# ProProject_PetCareSTM32_MiniSTM32_2024-0.net
KiCad netlist of a schematic drawn in EasyEDA Pro
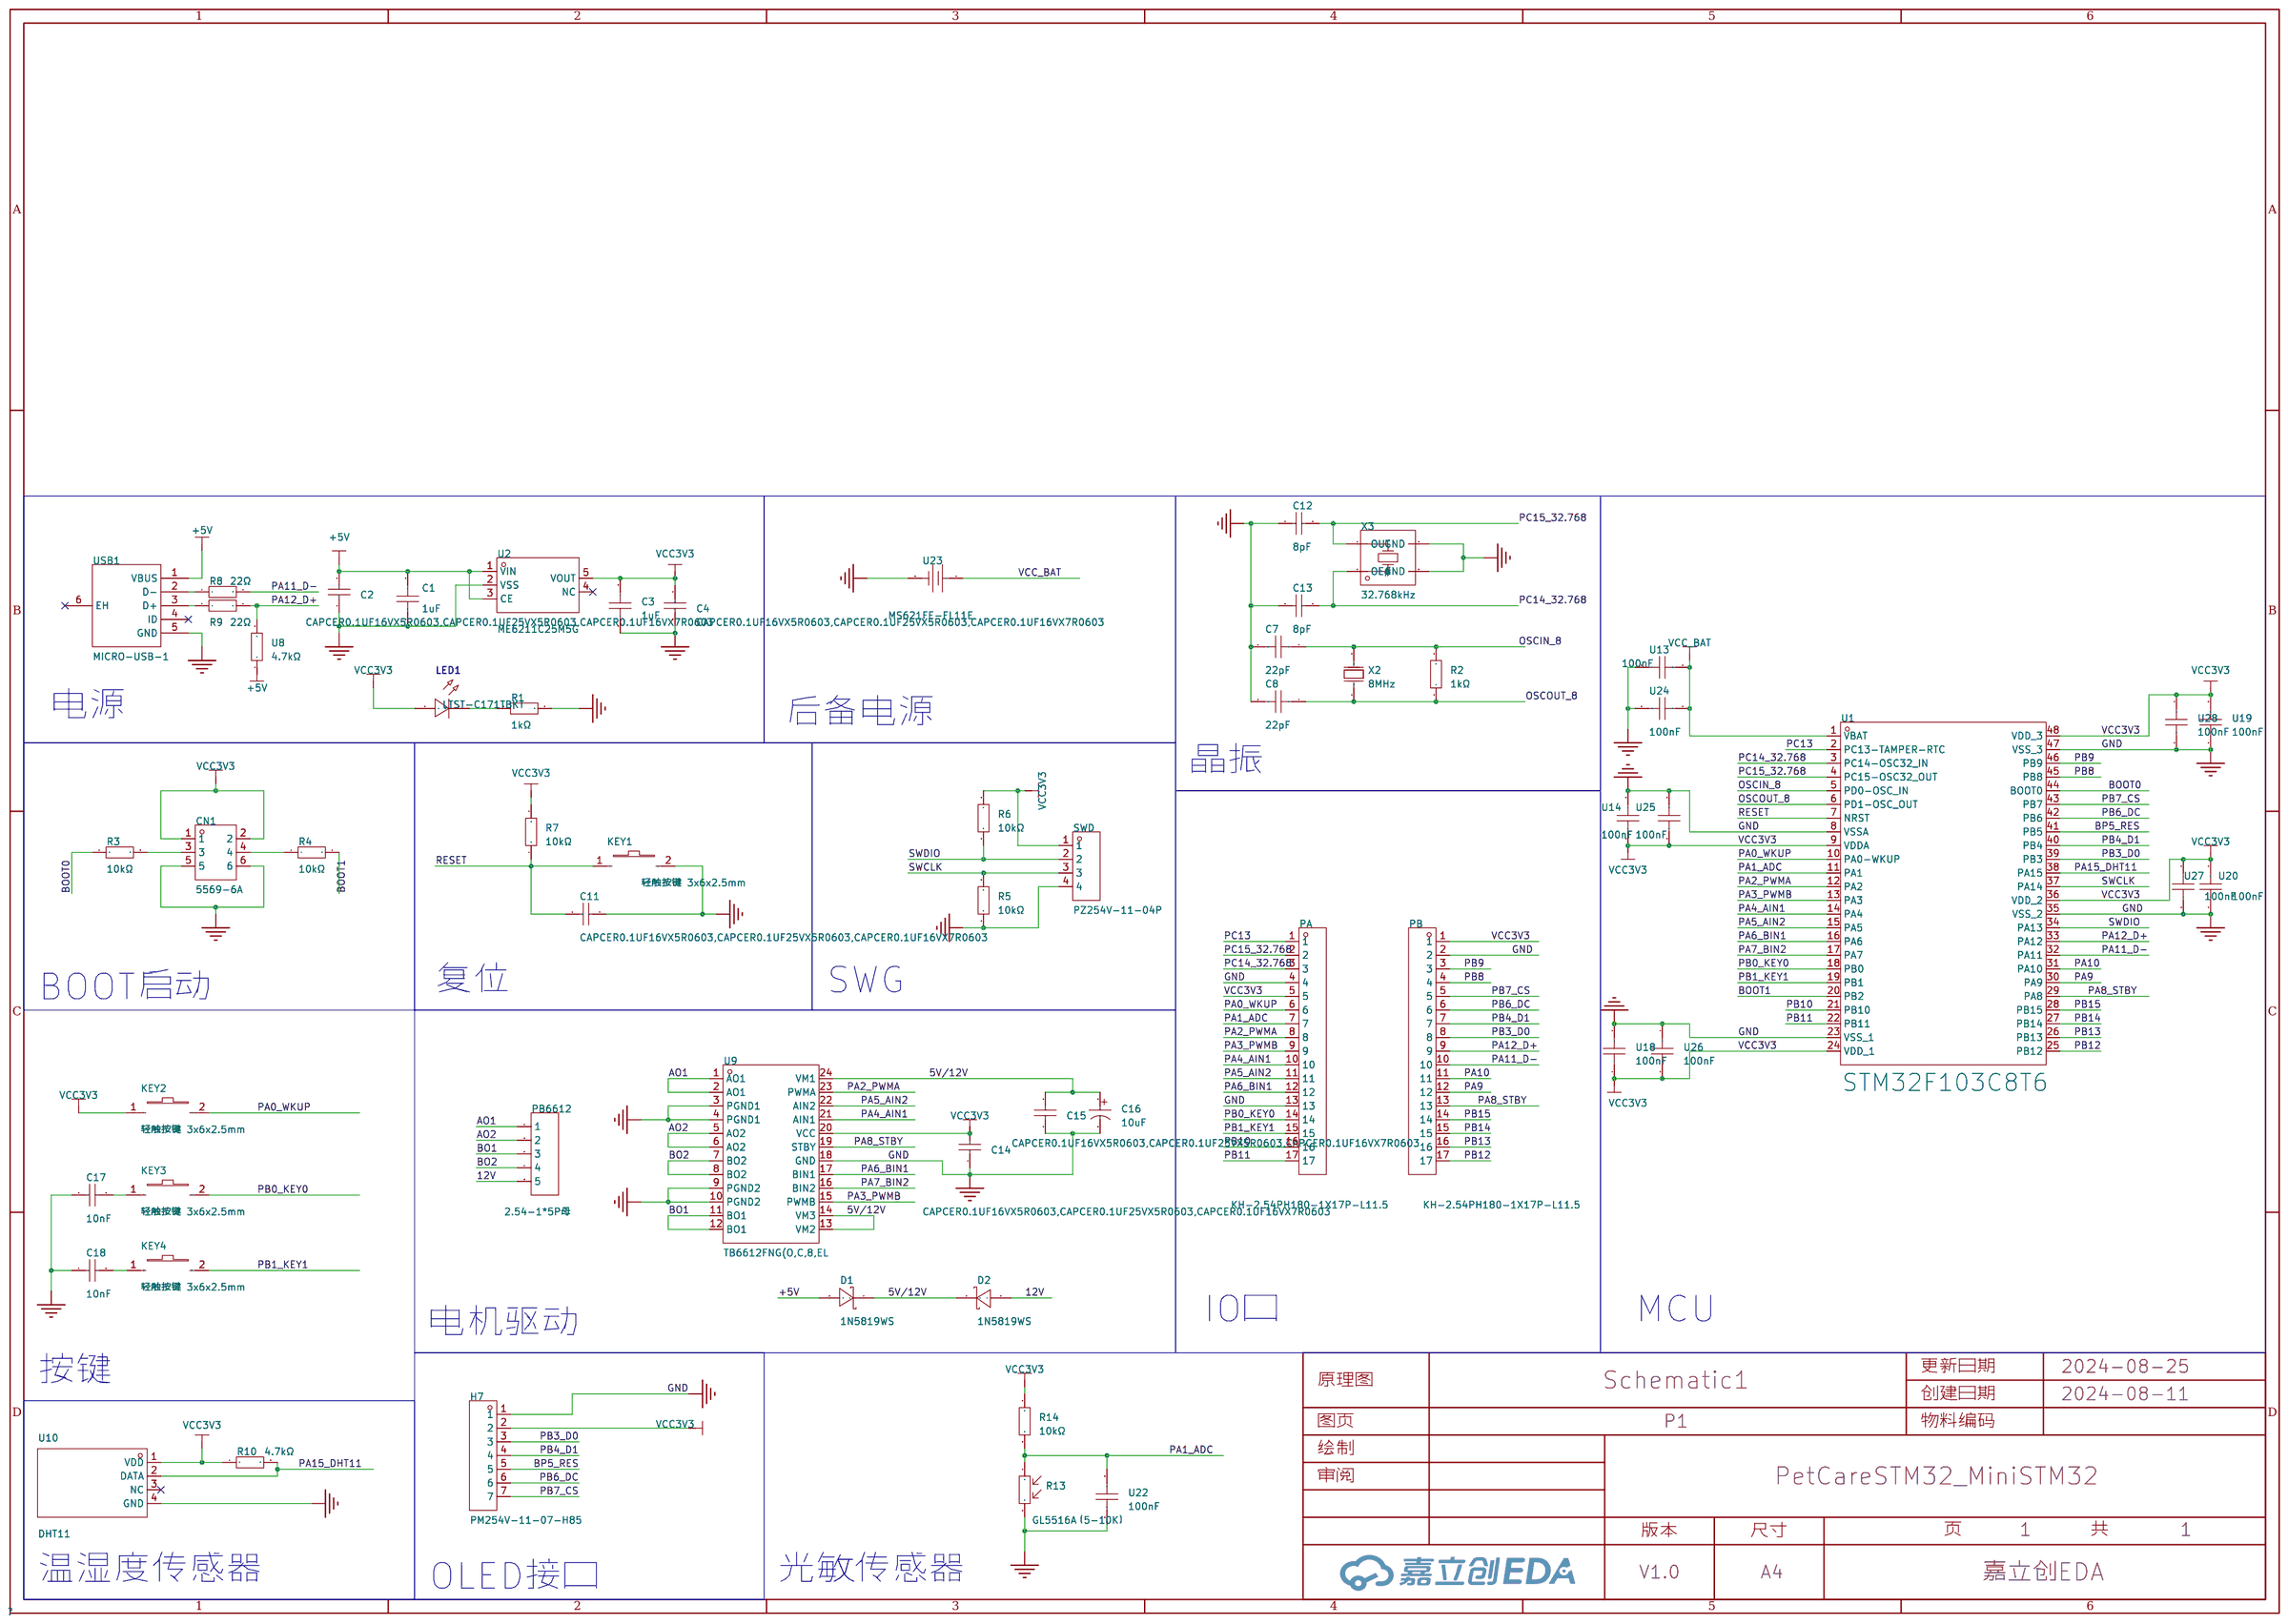
[diagram p0: schematic sheet]

(export (version "E")
  (design (tool "Eeschema 10.0.6"))
  (components
    (comp (ref "C1")
      (value "1uF")
      (footprint "easyedapro:C0603")
      (description "容值:1uF;精度:±10%;额定电压:50V;材质(温度系数):X5R;")
      (fields
        (field (name "Manufacturer Part") "CL10A105KB8NNNC")
        (field (name "Manufacturer") "SAMSUNG(三星)")
      )
      (libsource (lib "easyedapro") (part "CL10A105KB8NNNC"))
    )
    (comp (ref "C2")
      (value "CAPCER0.1UF16VX5R0603,CAPCER0.1UF25VX5R0603,CAPCER0.1UF16VX7R0603")
      (footprint "easyedapro:C0603")
      (libsource (lib "easyedapro") (part "CAPCER0.1UF16VX5R0603,CAPCER0.1UF25VX5R0603,CAPCER0.1UF16VX7R0603"))
    )
    (comp (ref "C3")
      (value "1uF")
      (footprint "easyedapro:C0603")
      (description "容值:1uF;精度:±10%;额定电压:50V;材质(温度系数):X5R;")
      (fields
        (field (name "Manufacturer Part") "CL10A105KB8NNNC")
        (field (name "Manufacturer") "SAMSUNG(三星)")
      )
      (libsource (lib "easyedapro") (part "CL10A105KB8NNNC"))
    )
    (comp (ref "C4")
      (value "CAPCER0.1UF16VX5R0603,CAPCER0.1UF25VX5R0603,CAPCER0.1UF16VX7R0603")
      (footprint "easyedapro:C0603")
      (libsource (lib "easyedapro") (part "CAPCER0.1UF16VX5R0603,CAPCER0.1UF25VX5R0603,CAPCER0.1UF16VX7R0603"))
    )
    (comp (ref "C7")
      (value "22pF")
      (footprint "easyedapro:C0603")
      (description "容值:22pF;精度:±5%;额定电压:50V;材质(温度系数):C0G;")
      (fields
        (field (name "Manufacturer Part") "CL10C220JB81PNC")
        (field (name "Manufacturer") "SAMSUNG(三星)")
      )
      (libsource (lib "easyedapro") (part "CL10C220JB81PNC"))
    )
    (comp (ref "C8")
      (value "22pF")
      (footprint "easyedapro:C0603")
      (description "容值:22pF;精度:±5%;额定电压:50V;材质(温度系数):C0G;")
      (fields
        (field (name "Manufacturer Part") "CL10C220JB81PNC")
        (field (name "Manufacturer") "SAMSUNG(三星)")
      )
      (libsource (lib "easyedapro") (part "CL10C220JB81PNC"))
    )
    (comp (ref "C11")
      (value "CAPCER0.1UF16VX5R0603,CAPCER0.1UF25VX5R0603,CAPCER0.1UF16VX7R0603")
      (footprint "easyedapro:C0603")
      (libsource (lib "easyedapro") (part "CAPCER0.1UF16VX5R0603,CAPCER0.1UF25VX5R0603,CAPCER0.1UF16VX7R0603"))
    )
    (comp (ref "C12")
      (value "8pF")
      (footprint "easyedapro:C0603")
      (description "容值:8pF;额定电压:50V;材质(温度系数):C0G;")
      (fields (field (name "Manufacturer Part") "0603CG8R0C500NT") (field (name "Manufacturer") "FH(风华)"))
      (libsource (lib "easyedapro") (part "0603CG8R0C500NT_C36508"))
    )
    (comp (ref "C13")
      (value "8pF")
      (footprint "easyedapro:C0603")
      (description "容值:8pF;额定电压:50V;材质(温度系数):C0G;")
      (fields (field (name "Manufacturer Part") "0603CG8R0C500NT") (field (name "Manufacturer") "FH(风华)"))
      (libsource (lib "easyedapro") (part "0603CG8R0C500NT_C36508"))
    )
    (comp (ref "C14")
      (value "CAPCER0.1UF16VX5R0603,CAPCER0.1UF25VX5R0603,CAPCER0.1UF16VX7R0603")
      (footprint "easyedapro:C0603")
      (libsource (lib "easyedapro") (part "CAPCER0.1UF16VX5R0603,CAPCER0.1UF25VX5R0603,CAPCER0.1UF16VX7R0603"))
    )
    (comp (ref "C15")
      (value "CAPCER0.1UF16VX5R0603,CAPCER0.1UF25VX5R0603,CAPCER0.1UF16VX7R0603")
      (footprint "easyedapro:C0603")
      (libsource (lib "easyedapro") (part "CAPCER0.1UF16VX5R0603,CAPCER0.1UF25VX5R0603,CAPCER0.1UF16VX7R0603"))
    )
    (comp (ref "C16")
      (value "10uF")
      (footprint "easyedapro:CAP-TH_BD5.0-P2.00-D0.8-FD")
      (description "容值:10uF;精度:±20%;额定电压:25V;")
      (fields (field (name "Manufacturer Part") "KF100M025C110A") (field (name "Manufacturer") "CapXon(丰宾)"))
      (libsource (lib "easyedapro") (part "KF100M025C110A"))
    )
    (comp (ref "C17")
      (value "10nF")
      (footprint "easyedapro:C0603")
      (description "容值:10nF;精度:±10%;额定电压:50V;材质(温度系数):X7R;")
      (fields
        (field (name "Manufacturer Part") "CC0603KRX7R9BB103")
        (field (name "Manufacturer") "YAGEO(国巨)")
      )
      (libsource (lib "easyedapro") (part "CC0603KRX7R9BB103"))
    )
    (comp (ref "C18")
      (value "10nF")
      (footprint "easyedapro:C0603")
      (description "容值:10nF;精度:±10%;额定电压:50V;材质(温度系数):X7R;")
      (fields
        (field (name "Manufacturer Part") "CC0603KRX7R9BB103")
        (field (name "Manufacturer") "YAGEO(国巨)")
      )
      (libsource (lib "easyedapro") (part "CC0603KRX7R9BB103"))
    )
    (comp (ref "CN1")
      (value "5569-6A")
      (footprint "easyedapro:CONN-TH_6P-P4.20_5569-6A-1")
      (libsource (lib "easyedapro") (part "5569-6A"))
    )
    (comp (ref "D1")
      (value "1N5819WS")
      (footprint "easyedapro:SOD-323_L1.8-W1.3-LS2.5-RD")
      (description "正向压降(Vf):600mV@1A;直流反向耐压(Vr):40V;平均整流电流(Io):1A;")
      (fields (field (name "Manufacturer") "Hottech(合科泰)"))
      (libsource (lib "easyedapro") (part "1N5819WS"))
    )
    (comp (ref "D2")
      (value "1N5819WS")
      (footprint "easyedapro:SOD-323_L1.8-W1.3-LS2.5-RD")
      (description "正向压降(Vf):600mV@1A;直流反向耐压(Vr):40V;平均整流电流(Io):1A;")
      (fields (field (name "Manufacturer") "Hottech(合科泰)"))
      (libsource (lib "easyedapro") (part "1N5819WS"))
    )
    (comp (ref "H7")
      (value "PM254V-11-07-H85")
      (footprint "easyedapro:HDR-TH_7P-P2.54-V-F")
      (fields (field (name "Manufacturer") "XFCN(兴飞)"))
      (libsource (lib "easyedapro") (part "PM254V-11-07-H85"))
    )
    (comp (ref "KEY1")
      (value "轻触按键 3x6x2.5mm")
      (footprint "easyedapro:SW-SMD_L6.0-W3.6-LS8.0")
      (libsource (lib "easyedapro") (part "3x6x2.5mm"))
    )
    (comp (ref "KEY2")
      (value "轻触按键 3x6x2.5mm")
      (footprint "easyedapro:SW-SMD_L6.0-W3.6-LS8.0")
      (libsource (lib "easyedapro") (part "3x6x2.5mm"))
    )
    (comp (ref "KEY3")
      (value "轻触按键 3x6x2.5mm")
      (footprint "easyedapro:SW-SMD_L6.0-W3.6-LS8.0")
      (libsource (lib "easyedapro") (part "3x6x2.5mm"))
    )
    (comp (ref "KEY4")
      (value "轻触按键 3x6x2.5mm")
      (footprint "easyedapro:SW-SMD_L6.0-W3.6-LS8.0")
      (libsource (lib "easyedapro") (part "3x6x2.5mm"))
    )
    (comp (ref "LED1")
      (value "LTST-C171TBKT")
      (footprint "easyedapro:LED_0805")
      (fields (field (name "Manufacturer") "LITEON(光宝)"))
      (libsource (lib "easyedapro") (part "LED_B"))
    )
    (comp (ref "PA")
      (value "KH-2.54PH180-1X17P-L11.5")
      (footprint "easyedapro:HDR-TH_17P-P2.54-V-M")
      (fields (field (name "Manufacturer") "kinghelm(金航标)"))
      (libsource (lib "easyedapro") (part "KH-2.54PH180-1X17P-L11.5"))
    )
    (comp (ref "PB")
      (value "KH-2.54PH180-1X17P-L11.5")
      (footprint "easyedapro:HDR-TH_17P-P2.54-V-M")
      (fields (field (name "Manufacturer") "kinghelm(金航标)"))
      (libsource (lib "easyedapro") (part "KH-2.54PH180-1X17P-L11.5"))
    )
    (comp (ref "PB6612")
      (value "2.54-1*5P母")
      (footprint "easyedapro:HDR-TH_5P-P2.54-V-F")
      (description "插孔结构:1x5P;间距:2.54mm;行距:-;安装类型:直插;排数:单排;总孔位数:5P;塑高:-;触头材质:-;触头镀层:-;")
      (fields (field (name "Manufacturer") "BOOMELE(博穆精密)"))
      (libsource (lib "easyedapro") (part "Header-Female-2.54_1x5"))
    )
    (comp (ref "R1")
      (value "1kΩ")
      (footprint "easyedapro:R0603")
      (description "电阻类型:厚膜电阻;阻值:1kΩ;精度:±1%;功率:100mW;最大工作电压:75V;温度系数:±100ppm/°C;")
      (fields (field (name "Manufacturer Part") "RC0603FR-071KL") (field (name "Manufacturer") "YAGEO(国巨)"))
      (libsource (lib "easyedapro") (part "RC0603FR-071KL"))
    )
    (comp (ref "R2")
      (value "1kΩ")
      (footprint "easyedapro:R0603")
      (description "电阻类型:厚膜电阻;阻值:1kΩ;精度:±0.5%;功率:100mW;最大工作电压:75V;温度系数:±100ppm/°C;")
      (fields
        (field (name "Manufacturer Part") "0603WAD1001T5E")
        (field (name "Manufacturer") "UNI-ROYAL(厚声)")
      )
      (libsource (lib "easyedapro") (part "0603WAD1001T5E"))
    )
    (comp (ref "R3")
      (value "10kΩ")
      (footprint "easyedapro:R0603")
      (description "电阻类型:厚膜电阻;阻值:10kΩ;精度:±1%;功率:100mW;最大工作电压:75V;温度系数:±100ppm/°C;")
      (fields
        (field (name "Manufacturer Part") "0603WAF1002T5E")
        (field (name "Manufacturer") "UNI-ROYAL(厚声)")
      )
      (libsource (lib "easyedapro") (part "0603WAF1002T5E"))
    )
    (comp (ref "R4")
      (value "10kΩ")
      (footprint "easyedapro:R0603")
      (description "电阻类型:厚膜电阻;阻值:10kΩ;精度:±1%;功率:100mW;最大工作电压:75V;温度系数:±100ppm/°C;")
      (fields
        (field (name "Manufacturer Part") "0603WAF1002T5E")
        (field (name "Manufacturer") "UNI-ROYAL(厚声)")
      )
      (libsource (lib "easyedapro") (part "0603WAF1002T5E"))
    )
    (comp (ref "R5")
      (value "10kΩ")
      (footprint "easyedapro:R0603")
      (description "电阻类型:厚膜电阻;阻值:10kΩ;精度:±1%;功率:100mW;最大工作电压:75V;温度系数:±100ppm/°C;")
      (fields
        (field (name "Manufacturer Part") "0603WAF1002T5E")
        (field (name "Manufacturer") "UNI-ROYAL(厚声)")
      )
      (libsource (lib "easyedapro") (part "0603WAF1002T5E"))
    )
    (comp (ref "R6")
      (value "10kΩ")
      (footprint "easyedapro:R0603")
      (description "电阻类型:厚膜电阻;阻值:10kΩ;精度:±1%;功率:100mW;最大工作电压:75V;温度系数:±100ppm/°C;")
      (fields
        (field (name "Manufacturer Part") "0603WAF1002T5E")
        (field (name "Manufacturer") "UNI-ROYAL(厚声)")
      )
      (libsource (lib "easyedapro") (part "0603WAF1002T5E"))
    )
    (comp (ref "R7")
      (value "10kΩ")
      (footprint "easyedapro:R0603")
      (description "电阻类型:厚膜电阻;阻值:10kΩ;精度:±1%;功率:100mW;最大工作电压:75V;温度系数:±100ppm/°C;")
      (fields
        (field (name "Manufacturer Part") "0603WAF1002T5E")
        (field (name "Manufacturer") "UNI-ROYAL(厚声)")
      )
      (libsource (lib "easyedapro") (part "0603WAF1002T5E"))
    )
    (comp (ref "R8")
      (value "22Ω")
      (footprint "easyedapro:R0805")
      (description "电阻类型:薄膜电阻;阻值:22Ω;精度:±1%;功率:250mW;最大工作电压:150V;温度系数:±25ppm/°C;")
      (fields
        (field (name "Manufacturer Part") "TC0525F220JT5E")
        (field (name "Manufacturer") "UNI-ROYAL(厚声)")
      )
      (libsource (lib "easyedapro") (part "TC0525F220JT5E"))
    )
    (comp (ref "R9")
      (value "22Ω")
      (footprint "easyedapro:R0805")
      (description "电阻类型:薄膜电阻;阻值:22Ω;精度:±1%;功率:250mW;最大工作电压:150V;温度系数:±25ppm/°C;")
      (fields
        (field (name "Manufacturer Part") "TC0525F220JT5E")
        (field (name "Manufacturer") "UNI-ROYAL(厚声)")
      )
      (libsource (lib "easyedapro") (part "TC0525F220JT5E"))
    )
    (comp (ref "R10")
      (value "4.7kΩ")
      (footprint "easyedapro:R1206")
      (description "电阻类型:厚膜电阻;阻值:4.7kΩ;精度:±1%;功率:250mW;最大工作电压:200V;温度系数:±100ppm/°C;")
      (fields
        (field (name "Manufacturer Part") "1206W4F4701T5E")
        (field (name "Manufacturer") "UNI-ROYAL(厚声)")
      )
      (libsource (lib "easyedapro") (part "1206W4F4701T5E"))
    )
    (comp (ref "R13")
      (value "GL5516A（5-10K）")
      (footprint "easyedapro:RES-TH_L5.1-W4.3-P3.40_GL55")
      (description "暗电阻:200kΩ;亮电阻 @ 10Lux:5kΩ~10kΩ;光谱峰值(波长):540nm;")
      (fields (field (name "Manufacturer") "JCHL(晶创和立)"))
      (libsource (lib "easyedapro") (part "GL5516A(5-10K)"))
    )
    (comp (ref "R14")
      (value "10kΩ")
      (footprint "easyedapro:R0603")
      (description "电阻类型:厚膜电阻;阻值:10kΩ;精度:±1%;功率:100mW;最大工作电压:75V;温度系数:±100ppm/°C;")
      (fields
        (field (name "Manufacturer Part") "0603WAF1002T5E")
        (field (name "Manufacturer") "UNI-ROYAL(厚声)")
      )
      (libsource (lib "easyedapro") (part "0603WAF1002T5E"))
    )
    (comp (ref "SWD")
      (value "PZ254V-11-04P")
      (footprint "easyedapro:HDR-TH_4P-P2.54-V-M")
      (fields (field (name "Manufacturer") "XFCN(兴飞)"))
      (libsource (lib "easyedapro") (part "PZ254V-11-04P_C2691448"))
    )
    (comp (ref "U1")
      (value "STM32F103C8T6")
      (footprint "easyedapro:LQFP-48_L7.0-W7.0-P0.50-LS9.0-BL")
      (description "CPU内核:ARM-M3;程序存储容量:64KB;RAM总容量:20KB;GPIO端口数量:37;工作电压范围:2V~3.6V;CPU最大主频:72MHz;程序存储器类型:FLASH;")
      (fields (field (name "Manufacturer") "ST(意法半导体)"))
      (libsource (lib "easyedapro") (part "STM32F103C8T6"))
    )
    (comp (ref "U2")
      (value "ME6211C25M5G")
      (footprint "easyedapro:SOT-23-5_L2.9-W1.7-P0.95-LS2.8-BL")
      (fields (field (name "Manufacturer") "MICRONE(南京微盟)"))
      (libsource (lib "easyedapro") (part "ME6211C25M5G"))
    )
    (comp (ref "U8")
      (value "4.7kΩ")
      (footprint "easyedapro:R0603")
      (description "电阻类型:薄膜电阻;阻值:4.7kΩ;精度:±1%;功率:100mW;最大工作电压:75V;温度系数:±50ppm/°C;")
      (fields (field (name "Manufacturer Part") "AR03FTDX4701A") (field (name "Manufacturer") "Viking(光颉)"))
      (libsource (lib "easyedapro") (part "AR03FTDX4701A"))
    )
    (comp (ref "U9")
      (value "TB6612FNG(O,C,8,EL")
      (footprint "easyedapro:SSOP-24_L8.4-W5.8-P0.65-LS7.8-BL")
      (description "双直流电机驱动器集成电路")
      (fields (field (name "Manufacturer") "TOSHIBA(东芝)"))
      (libsource (lib "easyedapro") (part "TB6612FNG(O,C,8,EL"))
    )
    (comp (ref "U10")
      (value "DHT11")
      (footprint "easyedapro:SENSOR-TH_DHT11")
      (description "新款电容式数字温湿度传感器,老款已停产16.1x12.6x5.8mm")
      (fields (field (name "Manufacturer") "广州奥松"))
      (libsource (lib "easyedapro") (part "DHT11"))
    )
    (comp (ref "U13")
      (value "100nF")
      (footprint "easyedapro:C0603")
      (description "容值:100nF;精度:±10%;额定电压:50V;材质(温度系数):X7R;")
      (fields
        (field (name "Manufacturer Part") "CGA0603X7R104K500JT")
        (field (name "Manufacturer") "HRE(芯声)")
      )
      (libsource (lib "easyedapro") (part "CGA0603X7R104K500JT"))
    )
    (comp (ref "U14")
      (value "100nF")
      (footprint "easyedapro:C0603")
      (description "容值:100nF;精度:±10%;额定电压:50V;材质(温度系数):X7R;")
      (fields
        (field (name "Manufacturer Part") "CGA0603X7R104K500JT")
        (field (name "Manufacturer") "HRE(芯声)")
      )
      (libsource (lib "easyedapro") (part "CGA0603X7R104K500JT"))
    )
    (comp (ref "U18")
      (value "100nF")
      (footprint "easyedapro:C0603")
      (description "容值:100nF;精度:±10%;额定电压:50V;材质(温度系数):X7R;")
      (fields
        (field (name "Manufacturer Part") "CGA0603X7R104K500JT")
        (field (name "Manufacturer") "HRE(芯声)")
      )
      (libsource (lib "easyedapro") (part "CGA0603X7R104K500JT"))
    )
    (comp (ref "U19")
      (value "100nF")
      (footprint "easyedapro:C0603")
      (description "容值:100nF;精度:±10%;额定电压:50V;材质(温度系数):X7R;")
      (fields
        (field (name "Manufacturer Part") "CGA0603X7R104K500JT")
        (field (name "Manufacturer") "HRE(芯声)")
      )
      (libsource (lib "easyedapro") (part "CGA0603X7R104K500JT"))
    )
    (comp (ref "U20")
      (value "100nF")
      (footprint "easyedapro:C0603")
      (description "容值:100nF;精度:±10%;额定电压:50V;材质(温度系数):X7R;")
      (fields
        (field (name "Manufacturer Part") "CGA0603X7R104K500JT")
        (field (name "Manufacturer") "HRE(芯声)")
      )
      (libsource (lib "easyedapro") (part "CGA0603X7R104K500JT"))
    )
    (comp (ref "U22")
      (value "100nF")
      (footprint "easyedapro:C0603")
      (description "容值:100nF;精度:±10%;额定电压:50V;材质(温度系数):X7R;")
      (fields
        (field (name "Manufacturer Part") "CGA0603X7R104K500JT")
        (field (name "Manufacturer") "HRE(芯声)")
      )
      (libsource (lib "easyedapro") (part "CGA0603X7R104K500JT"))
    )
    (comp (ref "U23")
      (value "MS621FE-FL11E")
      (footprint "easyedapro:BAT-SMD_FL11E")
      (description "FL11E 3.3V可充电纽扣电池 5.5mAH")
      (fields (field (name "Manufacturer") "Seiko(精工)"))
      (libsource (lib "easyedapro") (part "MS621FE-FL11E"))
    )
    (comp (ref "U24")
      (value "100nF")
      (footprint "easyedapro:C0603")
      (description "容值:100nF;精度:±10%;额定电压:50V;材质(温度系数):X7R;")
      (fields
        (field (name "Manufacturer Part") "CGA0603X7R104K500JT")
        (field (name "Manufacturer") "HRE(芯声)")
      )
      (libsource (lib "easyedapro") (part "CGA0603X7R104K500JT"))
    )
    (comp (ref "U25")
      (value "100nF")
      (footprint "easyedapro:C0603")
      (description "容值:100nF;精度:±10%;额定电压:50V;材质(温度系数):X7R;")
      (fields
        (field (name "Manufacturer Part") "CGA0603X7R104K500JT")
        (field (name "Manufacturer") "HRE(芯声)")
      )
      (libsource (lib "easyedapro") (part "CGA0603X7R104K500JT"))
    )
    (comp (ref "U26")
      (value "100nF")
      (footprint "easyedapro:C0603")
      (description "容值:100nF;精度:±10%;额定电压:50V;材质(温度系数):X7R;")
      (fields
        (field (name "Manufacturer Part") "CGA0603X7R104K500JT")
        (field (name "Manufacturer") "HRE(芯声)")
      )
      (libsource (lib "easyedapro") (part "CGA0603X7R104K500JT"))
    )
    (comp (ref "U27")
      (value "100nF")
      (footprint "easyedapro:C0603")
      (description "容值:100nF;精度:±10%;额定电压:50V;材质(温度系数):X7R;")
      (fields
        (field (name "Manufacturer Part") "CGA0603X7R104K500JT")
        (field (name "Manufacturer") "HRE(芯声)")
      )
      (libsource (lib "easyedapro") (part "CGA0603X7R104K500JT"))
    )
    (comp (ref "U28")
      (value "100nF")
      (footprint "easyedapro:C0603")
      (description "容值:100nF;精度:±10%;额定电压:50V;材质(温度系数):X7R;")
      (fields
        (field (name "Manufacturer Part") "CGA0603X7R104K500JT")
        (field (name "Manufacturer") "HRE(芯声)")
      )
      (libsource (lib "easyedapro") (part "CGA0603X7R104K500JT"))
    )
    (comp (ref "USB1")
      (value "MICRO-USB-1")
      (footprint "easyedapro:MICRO-USB-SMD_C9900008946")
      (libsource (lib "easyedapro") (part "MICRO-USB-1"))
    )
    (comp (ref "X2")
      (value "8MHz")
      (footprint "easyedapro:OSC-SMD_L5.0-W3.2")
      (description "晶振类型:贴片晶振;频率:8MHz;常温频差:±20ppm;外接负载电容:18pF;频率稳定度(全温):±30ppm;")
      (fields
        (field (name "Manufacturer Part") "ABM3-8.000MHZ-D2Y-T")
        (field (name "Manufacturer") "ABRACON")
      )
      (libsource (lib "easyedapro") (part "ABM3-8.000MHZ-D2Y-T"))
    )
    (comp (ref "X3")
      (value "32.768kHz")
      (footprint "easyedapro:CRYSTAL-SMD_4P-L8.0-W3.8-BL")
      (description "晶振类型:-;频率:32.768kHz;常温频差:±20ppm;外接负载电容:12.5pF;频率稳定度(全温):-;")
      (fields (field (name "Manufacturer Part") "ABS25-32.768KHZ-T") (field (name "Manufacturer") "ABRACON"))
      (libsource (lib "easyedapro") (part "ABS25-32.768KHZ-T"))
    )
  )
  (nets
    (net (code "1") (name "+5V") (class "Default")
      (node (ref "C1") (pin "2") (pinfunction "2_2") (pintype "unspecified"))
      (node (ref "C2") (pin "2") (pinfunction "2_2") (pintype "input"))
      (node (ref "D1") (pin "2") (pinfunction "A_2") (pintype "unspecified"))
      (node (ref "U2") (pin "1") (pinfunction "VIN_1") (pintype "unspecified"))
      (node (ref "U2") (pin "3") (pinfunction "CE_3") (pintype "unspecified"))
      (node (ref "U8") (pin "1") (pinfunction "1_1") (pintype "unspecified"))
      (node (ref "USB1") (pin "1") (pinfunction "VBUS_1") (pintype "input"))
    )
    (net (code "2") (name "/5V{slash}12V") (class "Default")
      (node (ref "C15") (pin "2") (pinfunction "2_2") (pintype "input"))
      (node (ref "C16") (pin "1") (pinfunction "1_1") (pintype "input"))
      (node (ref "D1") (pin "1") (pinfunction "K_1") (pintype "unspecified"))
      (node (ref "D2") (pin "1") (pinfunction "K_1") (pintype "unspecified"))
      (node (ref "U9") (pin "13") (pinfunction "VM2_13") (pintype "unspecified"))
      (node (ref "U9") (pin "14") (pinfunction "VM3_14") (pintype "unspecified"))
      (node (ref "U9") (pin "24") (pinfunction "VM1_24") (pintype "unspecified"))
    )
    (net (code "3") (name "/12V") (class "Default")
      (node (ref "D2") (pin "2") (pinfunction "A_2") (pintype "unspecified"))
      (node (ref "PB6612") (pin "5") (pinfunction "5_5") (pintype "input"))
    )
    (net (code "4") (name "/AO1") (class "Default")
      (node (ref "PB6612") (pin "1") (pinfunction "1_1") (pintype "input"))
      (node (ref "U9") (pin "1") (pinfunction "AO1_1") (pintype "unspecified"))
      (node (ref "U9") (pin "2") (pinfunction "AO1_2") (pintype "unspecified"))
    )
    (net (code "5") (name "/AO2") (class "Default")
      (node (ref "PB6612") (pin "2") (pinfunction "2_2") (pintype "input"))
      (node (ref "U9") (pin "5") (pinfunction "AO2_5") (pintype "unspecified"))
      (node (ref "U9") (pin "6") (pinfunction "AO2_6") (pintype "unspecified"))
    )
    (net (code "6") (name "/BO1") (class "Default")
      (node (ref "PB6612") (pin "3") (pinfunction "3_3") (pintype "input"))
      (node (ref "U9") (pin "11") (pinfunction "BO1_11") (pintype "unspecified"))
      (node (ref "U9") (pin "12") (pinfunction "BO1_12") (pintype "unspecified"))
    )
    (net (code "7") (name "/BO2") (class "Default")
      (node (ref "PB6612") (pin "4") (pinfunction "4_4") (pintype "input"))
      (node (ref "U9") (pin "7") (pinfunction "BO2_7") (pintype "unspecified"))
      (node (ref "U9") (pin "8") (pinfunction "BO2_8") (pintype "unspecified"))
    )
    (net (code "8") (name "/BOOT0") (class "Default")
      (node (ref "R3") (pin "1") (pinfunction "1_1") (pintype "input"))
      (node (ref "U1") (pin "44") (pinfunction "BOOT0_44") (pintype "unspecified"))
    )
    (net (code "9") (name "/BOOT1") (class "Default")
      (node (ref "R4") (pin "2") (pinfunction "2_2") (pintype "input"))
      (node (ref "U1") (pin "20") (pinfunction "PB2_20") (pintype "unspecified"))
    )
    (net (code "10") (name "/BP5_RES") (class "Default")
      (node (ref "H7") (pin "5") (pinfunction "5_5") (pintype "unspecified"))
      (node (ref "U1") (pin "41") (pinfunction "PB5_41") (pintype "unspecified"))
    )
    (net (code "11") (name "/OSCIN_8") (class "Default")
      (node (ref "C7") (pin "1") (pinfunction "1_1") (pintype "unspecified"))
      (node (ref "R2") (pin "2") (pinfunction "2_2") (pintype "input"))
      (node (ref "U1") (pin "5") (pinfunction "PD0-OSC_IN_5") (pintype "unspecified"))
      (node (ref "X2") (pin "2") (pinfunction "OSC2_2") (pintype "input"))
    )
    (net (code "12") (name "/OSCOUT_8") (class "Default")
      (node (ref "C8") (pin "1") (pinfunction "1_1") (pintype "unspecified"))
      (node (ref "R2") (pin "1") (pinfunction "1_1") (pintype "input"))
      (node (ref "U1") (pin "6") (pinfunction "PD1-OSC_OUT_6") (pintype "unspecified"))
      (node (ref "X2") (pin "1") (pinfunction "OSC1_1") (pintype "input"))
    )
    (net (code "13") (name "/PA0_WKUP") (class "Default")
      (node (ref "KEY2") (pin "2") (pinfunction "2_2") (pintype "input"))
      (node (ref "PA") (pin "6") (pinfunction "6_6") (pintype "unspecified"))
      (node (ref "U1") (pin "10") (pinfunction "PA0-WKUP_10") (pintype "unspecified"))
    )
    (net (code "14") (name "/PA1_ADC") (class "Default")
      (node (ref "PA") (pin "7") (pinfunction "7_7") (pintype "unspecified"))
      (node (ref "R13") (pin "1") (pinfunction "1_1") (pintype "input"))
      (node (ref "R14") (pin "1") (pinfunction "1_1") (pintype "input"))
      (node (ref "U1") (pin "11") (pinfunction "PA1_11") (pintype "unspecified"))
      (node (ref "U22") (pin "2") (pinfunction "2_2") (pintype "unspecified"))
    )
    (net (code "15") (name "/PA2_PWMA") (class "Default")
      (node (ref "PA") (pin "8") (pinfunction "8_8") (pintype "unspecified"))
      (node (ref "U1") (pin "12") (pinfunction "PA2_12") (pintype "unspecified"))
      (node (ref "U9") (pin "23") (pinfunction "PWMA_23") (pintype "unspecified"))
    )
    (net (code "16") (name "/PA3_PWMB") (class "Default")
      (node (ref "PA") (pin "9") (pinfunction "9_9") (pintype "unspecified"))
      (node (ref "U1") (pin "13") (pinfunction "PA3_13") (pintype "unspecified"))
      (node (ref "U9") (pin "15") (pinfunction "PWMB_15") (pintype "unspecified"))
    )
    (net (code "17") (name "/PA4_AIN1") (class "Default")
      (node (ref "PA") (pin "10") (pinfunction "10_10") (pintype "unspecified"))
      (node (ref "U1") (pin "14") (pinfunction "PA4_14") (pintype "unspecified"))
      (node (ref "U9") (pin "21") (pinfunction "AIN1_21") (pintype "unspecified"))
    )
    (net (code "18") (name "/PA5_AIN2") (class "Default")
      (node (ref "PA") (pin "11") (pinfunction "11_11") (pintype "unspecified"))
      (node (ref "U1") (pin "15") (pinfunction "PA5_15") (pintype "unspecified"))
      (node (ref "U9") (pin "22") (pinfunction "AIN2_22") (pintype "unspecified"))
    )
    (net (code "19") (name "/PA6_BIN1") (class "Default")
      (node (ref "PA") (pin "12") (pinfunction "12_12") (pintype "unspecified"))
      (node (ref "U1") (pin "16") (pinfunction "PA6_16") (pintype "unspecified"))
      (node (ref "U9") (pin "17") (pinfunction "BIN1_17") (pintype "unspecified"))
    )
    (net (code "20") (name "/PA7_BIN2") (class "Default")
      (node (ref "U1") (pin "17") (pinfunction "PA7_17") (pintype "unspecified"))
      (node (ref "U9") (pin "16") (pinfunction "BIN2_16") (pintype "unspecified"))
    )
    (net (code "21") (name "/PA8_STBY") (class "Default")
      (node (ref "PB") (pin "13") (pinfunction "13_13") (pintype "unspecified"))
      (node (ref "U1") (pin "29") (pinfunction "PA8_29") (pintype "unspecified"))
      (node (ref "U9") (pin "19") (pinfunction "STBY_19") (pintype "unspecified"))
    )
    (net (code "22") (name "/PA9") (class "Default")
      (node (ref "PB") (pin "12") (pinfunction "12_12") (pintype "unspecified"))
      (node (ref "U1") (pin "30") (pinfunction "PA9_30") (pintype "unspecified"))
    )
    (net (code "23") (name "/PA10") (class "Default")
      (node (ref "PB") (pin "11") (pinfunction "11_11") (pintype "unspecified"))
      (node (ref "U1") (pin "31") (pinfunction "PA10_31") (pintype "unspecified"))
    )
    (net (code "24") (name "/PA11_D-") (class "Default")
      (node (ref "PB") (pin "10") (pinfunction "10_10") (pintype "unspecified"))
      (node (ref "R8") (pin "2") (pinfunction "2_2") (pintype "input"))
      (node (ref "U1") (pin "32") (pinfunction "PA11_32") (pintype "unspecified"))
    )
    (net (code "25") (name "/PA12_D+") (class "Default")
      (node (ref "PB") (pin "9") (pinfunction "9_9") (pintype "unspecified"))
      (node (ref "R9") (pin "2") (pinfunction "2_2") (pintype "input"))
      (node (ref "U1") (pin "33") (pinfunction "PA12_33") (pintype "unspecified"))
      (node (ref "U8") (pin "2") (pinfunction "2_2") (pintype "unspecified"))
    )
    (net (code "26") (name "/PA15_DHT11") (class "Default")
      (node (ref "R10") (pin "2") (pinfunction "2_2") (pintype "input"))
      (node (ref "U1") (pin "38") (pinfunction "PA15_38") (pintype "unspecified"))
      (node (ref "U10") (pin "2") (pinfunction "DATA_2") (pintype "unspecified"))
    )
    (net (code "27") (name "/PB0_KEY0") (class "Default")
      (node (ref "KEY3") (pin "2") (pinfunction "2_2") (pintype "input"))
      (node (ref "PA") (pin "14") (pinfunction "14_14") (pintype "unspecified"))
      (node (ref "U1") (pin "18") (pinfunction "PB0_18") (pintype "unspecified"))
    )
    (net (code "28") (name "/PB1_KEY1") (class "Default")
      (node (ref "KEY4") (pin "2") (pinfunction "2_2") (pintype "input"))
      (node (ref "PA") (pin "15") (pinfunction "15_15") (pintype "unspecified"))
      (node (ref "U1") (pin "19") (pinfunction "PB1_19") (pintype "unspecified"))
    )
    (net (code "29") (name "/PB3_D0") (class "Default")
      (node (ref "H7") (pin "3") (pinfunction "3_3") (pintype "unspecified"))
      (node (ref "PB") (pin "8") (pinfunction "8_8") (pintype "unspecified"))
      (node (ref "U1") (pin "39") (pinfunction "PB3_39") (pintype "unspecified"))
    )
    (net (code "30") (name "/PB4_D1") (class "Default")
      (node (ref "H7") (pin "4") (pinfunction "4_4") (pintype "unspecified"))
      (node (ref "PB") (pin "7") (pinfunction "7_7") (pintype "unspecified"))
      (node (ref "U1") (pin "40") (pinfunction "PB4_40") (pintype "unspecified"))
    )
    (net (code "31") (name "/PB6_DC") (class "Default")
      (node (ref "H7") (pin "6") (pinfunction "6_6") (pintype "unspecified"))
      (node (ref "PB") (pin "6") (pinfunction "6_6") (pintype "unspecified"))
      (node (ref "U1") (pin "42") (pinfunction "PB6_42") (pintype "unspecified"))
    )
    (net (code "32") (name "/PB7_CS") (class "Default")
      (node (ref "H7") (pin "7") (pinfunction "7_7") (pintype "unspecified"))
      (node (ref "PB") (pin "5") (pinfunction "5_5") (pintype "unspecified"))
      (node (ref "U1") (pin "43") (pinfunction "PB7_43") (pintype "unspecified"))
    )
    (net (code "33") (name "/PB8") (class "Default")
      (node (ref "PB") (pin "4") (pinfunction "4_4") (pintype "unspecified"))
      (node (ref "U1") (pin "45") (pinfunction "PB8_45") (pintype "unspecified"))
    )
    (net (code "34") (name "/PB9") (class "Default")
      (node (ref "PB") (pin "3") (pinfunction "3_3") (pintype "unspecified"))
      (node (ref "U1") (pin "46") (pinfunction "PB9_46") (pintype "unspecified"))
    )
    (net (code "35") (name "/PB10") (class "Default")
      (node (ref "PA") (pin "16") (pinfunction "16_16") (pintype "unspecified"))
      (node (ref "U1") (pin "21") (pinfunction "PB10_21") (pintype "unspecified"))
    )
    (net (code "36") (name "/PB11") (class "Default")
      (node (ref "PA") (pin "17") (pinfunction "17_17") (pintype "unspecified"))
      (node (ref "U1") (pin "22") (pinfunction "PB11_22") (pintype "unspecified"))
    )
    (net (code "37") (name "/PB12") (class "Default")
      (node (ref "PB") (pin "17") (pinfunction "17_17") (pintype "unspecified"))
      (node (ref "U1") (pin "25") (pinfunction "PB12_25") (pintype "unspecified"))
    )
    (net (code "38") (name "/PB13") (class "Default")
      (node (ref "PB") (pin "16") (pinfunction "16_16") (pintype "unspecified"))
      (node (ref "U1") (pin "26") (pinfunction "PB13_26") (pintype "unspecified"))
    )
    (net (code "39") (name "/PB14") (class "Default")
      (node (ref "PB") (pin "15") (pinfunction "15_15") (pintype "unspecified"))
      (node (ref "U1") (pin "27") (pinfunction "PB14_27") (pintype "unspecified"))
    )
    (net (code "40") (name "/PB15") (class "Default")
      (node (ref "PB") (pin "14") (pinfunction "14_14") (pintype "unspecified"))
      (node (ref "U1") (pin "28") (pinfunction "PB15_28") (pintype "unspecified"))
    )
    (net (code "41") (name "/PC13") (class "Default")
      (node (ref "PA") (pin "1") (pinfunction "1_1") (pintype "unspecified"))
      (node (ref "U1") (pin "2") (pinfunction "PC13-TAMPER-RTC_2") (pintype "unspecified"))
    )
    (net (code "42") (name "/PC14_32.768") (class "Default")
      (node (ref "C13") (pin "2") (pinfunction "2_2") (pintype "input"))
      (node (ref "PA") (pin "3") (pinfunction "3_3") (pintype "unspecified"))
      (node (ref "U1") (pin "3") (pinfunction "PC14-OSC32_IN_3") (pintype "unspecified"))
      (node (ref "X3") (pin "1") (pinfunction "OE#_1") (pintype "input"))
    )
    (net (code "43") (name "/PC15_32.768") (class "Default")
      (node (ref "C12") (pin "2") (pinfunction "2_2") (pintype "input"))
      (node (ref "PA") (pin "2") (pinfunction "2_2") (pintype "unspecified"))
      (node (ref "U1") (pin "4") (pinfunction "PC15-OSC32_OUT_4") (pintype "unspecified"))
      (node (ref "X3") (pin "4") (pinfunction "OUT_4") (pintype "input"))
    )
    (net (code "44") (name "/RESET") (class "Default")
      (node (ref "C11") (pin "1") (pinfunction "1_1") (pintype "input"))
      (node (ref "KEY1") (pin "1") (pinfunction "1_1") (pintype "input"))
      (node (ref "R7") (pin "1") (pinfunction "1_1") (pintype "input"))
      (node (ref "U1") (pin "7") (pinfunction "NRST_7") (pintype "unspecified"))
    )
    (net (code "45") (name "/SWCLK") (class "Default")
      (node (ref "R5") (pin "2") (pinfunction "2_2") (pintype "input"))
      (node (ref "SWD") (pin "3") (pinfunction "3_3") (pintype "unspecified"))
      (node (ref "U1") (pin "37") (pinfunction "PA14_37") (pintype "unspecified"))
    )
    (net (code "46") (name "/SWDIO") (class "Default")
      (node (ref "R6") (pin "1") (pinfunction "1_1") (pintype "input"))
      (node (ref "SWD") (pin "2") (pinfunction "2_2") (pintype "unspecified"))
      (node (ref "U1") (pin "34") (pinfunction "PA13_34") (pintype "unspecified"))
    )
    (net (code "47") (name "GND") (class "Default")
      (node (ref "C1") (pin "1") (pinfunction "1_1") (pintype "unspecified"))
      (node (ref "C11") (pin "2") (pinfunction "2_2") (pintype "input"))
      (node (ref "C12") (pin "1") (pinfunction "1_1") (pintype "input"))
      (node (ref "C13") (pin "1") (pinfunction "1_1") (pintype "input"))
      (node (ref "C14") (pin "1") (pinfunction "1_1") (pintype "input"))
      (node (ref "C15") (pin "1") (pinfunction "1_1") (pintype "input"))
      (node (ref "C16") (pin "2") (pinfunction "2_2") (pintype "input"))
      (node (ref "C17") (pin "2") (pinfunction "2_2") (pintype "input"))
      (node (ref "C18") (pin "1") (pinfunction "1_1") (pintype "input"))
      (node (ref "C2") (pin "1") (pinfunction "1_1") (pintype "input"))
      (node (ref "C3") (pin "1") (pinfunction "1_1") (pintype "unspecified"))
      (node (ref "C4") (pin "1") (pinfunction "1_1") (pintype "input"))
      (node (ref "C7") (pin "2") (pinfunction "2_2") (pintype "unspecified"))
      (node (ref "C8") (pin "2") (pinfunction "2_2") (pintype "unspecified"))
      (node (ref "CN1") (pin "5") (pinfunction "5_5") (pintype "unspecified"))
      (node (ref "CN1") (pin "6") (pinfunction "6_6") (pintype "unspecified"))
      (node (ref "H7") (pin "1") (pinfunction "1_1") (pintype "unspecified"))
      (node (ref "KEY1") (pin "2") (pinfunction "2_2") (pintype "input"))
      (node (ref "PA") (pin "13") (pinfunction "13_13") (pintype "unspecified"))
      (node (ref "PA") (pin "4") (pinfunction "4_4") (pintype "unspecified"))
      (node (ref "PB") (pin "2") (pinfunction "2_2") (pintype "unspecified"))
      (node (ref "R1") (pin "2") (pinfunction "2_2") (pintype "input"))
      (node (ref "R13") (pin "2") (pinfunction "2_2") (pintype "input"))
      (node (ref "R5") (pin "1") (pinfunction "1_1") (pintype "input"))
      (node (ref "SWD") (pin "4") (pinfunction "4_4") (pintype "unspecified"))
      (node (ref "U1") (pin "23") (pinfunction "VSS_1_23") (pintype "unspecified"))
      (node (ref "U1") (pin "35") (pinfunction "VSS_2_35") (pintype "unspecified"))
      (node (ref "U1") (pin "47") (pinfunction "VSS_3_47") (pintype "unspecified"))
      (node (ref "U1") (pin "8") (pinfunction "VSSA_8") (pintype "unspecified"))
      (node (ref "U10") (pin "4") (pinfunction "GND_4") (pintype "unspecified"))
      (node (ref "U13") (pin "2") (pinfunction "2_2") (pintype "unspecified"))
      (node (ref "U14") (pin "2") (pinfunction "2_2") (pintype "unspecified"))
      (node (ref "U18") (pin "2") (pinfunction "2_2") (pintype "unspecified"))
      (node (ref "U19") (pin "1") (pinfunction "1_1") (pintype "unspecified"))
      (node (ref "U2") (pin "2") (pinfunction "VSS_2") (pintype "unspecified"))
      (node (ref "U20") (pin "1") (pinfunction "1_1") (pintype "unspecified"))
      (node (ref "U22") (pin "1") (pinfunction "1_1") (pintype "unspecified"))
      (node (ref "U23") (pin "2") (pinfunction "-_2") (pintype "unspecified"))
      (node (ref "U24") (pin "2") (pinfunction "2_2") (pintype "unspecified"))
      (node (ref "U25") (pin "1") (pinfunction "1_1") (pintype "unspecified"))
      (node (ref "U26") (pin "1") (pinfunction "1_1") (pintype "unspecified"))
      (node (ref "U27") (pin "2") (pinfunction "2_2") (pintype "unspecified"))
      (node (ref "U28") (pin "2") (pinfunction "2_2") (pintype "unspecified"))
      (node (ref "U9") (pin "10") (pinfunction "PGND2_10") (pintype "unspecified"))
      (node (ref "U9") (pin "18") (pinfunction "GND_18") (pintype "unspecified"))
      (node (ref "U9") (pin "3") (pinfunction "PGND1_3") (pintype "unspecified"))
      (node (ref "U9") (pin "4") (pinfunction "PGND1_4") (pintype "unspecified"))
      (node (ref "U9") (pin "9") (pinfunction "PGND2_9") (pintype "unspecified"))
      (node (ref "USB1") (pin "5") (pinfunction "GND_5") (pintype "input"))
      (node (ref "X3") (pin "2") (pinfunction "GND_2") (pintype "input"))
      (node (ref "X3") (pin "3") (pinfunction "GND_3") (pintype "input"))
    )
    (net (code "48") (name "Net-(C17-Pad1)") (class "Default")
      (node (ref "C17") (pin "1") (pinfunction "1_1") (pintype "input"))
      (node (ref "KEY3") (pin "1") (pinfunction "1_1") (pintype "input"))
    )
    (net (code "49") (name "Net-(C18-Pad2)") (class "Default")
      (node (ref "C18") (pin "2") (pinfunction "2_2") (pintype "input"))
      (node (ref "KEY4") (pin "1") (pinfunction "1_1") (pintype "input"))
    )
    (net (code "50") (name "Net-(CN1-Pad3)") (class "Default")
      (node (ref "CN1") (pin "3") (pinfunction "3_3") (pintype "unspecified"))
      (node (ref "R3") (pin "2") (pinfunction "2_2") (pintype "input"))
    )
    (net (code "51") (name "Net-(CN1-Pad4)") (class "Default")
      (node (ref "CN1") (pin "4") (pinfunction "4_4") (pintype "unspecified"))
      (node (ref "R4") (pin "1") (pinfunction "1_1") (pintype "input"))
    )
    (net (code "52") (name "Net-(LED1-C)") (class "Default")
      (node (ref "LED1") (pin "1") (pinfunction "C_1") (pintype "input"))
      (node (ref "R1") (pin "1") (pinfunction "1_1") (pintype "input"))
    )
    (net (code "53") (name "Net-(USB1-D+)") (class "Default")
      (node (ref "R9") (pin "1") (pinfunction "1_1") (pintype "input"))
      (node (ref "USB1") (pin "3") (pinfunction "D+_3") (pintype "input"))
    )
    (net (code "54") (name "Net-(USB1-D-)") (class "Default")
      (node (ref "R8") (pin "1") (pinfunction "1_1") (pintype "input"))
      (node (ref "USB1") (pin "2") (pinfunction "D-_2") (pintype "input"))
    )
    (net (code "55") (name "VCC3V3") (class "Default")
      (node (ref "C14") (pin "2") (pinfunction "2_2") (pintype "input"))
      (node (ref "C3") (pin "2") (pinfunction "2_2") (pintype "unspecified"))
      (node (ref "C4") (pin "2") (pinfunction "2_2") (pintype "input"))
      (node (ref "CN1") (pin "1") (pinfunction "1_1") (pintype "unspecified"))
      (node (ref "CN1") (pin "2") (pinfunction "2_2") (pintype "unspecified"))
      (node (ref "H7") (pin "2") (pinfunction "2_2") (pintype "unspecified"))
      (node (ref "KEY2") (pin "1") (pinfunction "1_1") (pintype "input"))
      (node (ref "LED1") (pin "2") (pinfunction "A_2") (pintype "input"))
      (node (ref "PA") (pin "5") (pinfunction "5_5") (pintype "unspecified"))
      (node (ref "PB") (pin "1") (pinfunction "1_1") (pintype "unspecified"))
      (node (ref "R10") (pin "1") (pinfunction "1_1") (pintype "input"))
      (node (ref "R14") (pin "2") (pinfunction "2_2") (pintype "input"))
      (node (ref "R6") (pin "2") (pinfunction "2_2") (pintype "input"))
      (node (ref "R7") (pin "2") (pinfunction "2_2") (pintype "input"))
      (node (ref "SWD") (pin "1") (pinfunction "1_1") (pintype "unspecified"))
      (node (ref "U1") (pin "24") (pinfunction "VDD_1_24") (pintype "unspecified"))
      (node (ref "U1") (pin "36") (pinfunction "VDD_2_36") (pintype "unspecified"))
      (node (ref "U1") (pin "48") (pinfunction "VDD_3_48") (pintype "unspecified"))
      (node (ref "U1") (pin "9") (pinfunction "VDDA_9") (pintype "unspecified"))
      (node (ref "U10") (pin "1") (pinfunction "VDD_1") (pintype "unspecified"))
      (node (ref "U14") (pin "1") (pinfunction "1_1") (pintype "unspecified"))
      (node (ref "U18") (pin "1") (pinfunction "1_1") (pintype "unspecified"))
      (node (ref "U19") (pin "2") (pinfunction "2_2") (pintype "unspecified"))
      (node (ref "U2") (pin "5") (pinfunction "VOUT_5") (pintype "unspecified"))
      (node (ref "U20") (pin "2") (pinfunction "2_2") (pintype "unspecified"))
      (node (ref "U25") (pin "2") (pinfunction "2_2") (pintype "unspecified"))
      (node (ref "U26") (pin "2") (pinfunction "2_2") (pintype "unspecified"))
      (node (ref "U27") (pin "1") (pinfunction "1_1") (pintype "unspecified"))
      (node (ref "U28") (pin "1") (pinfunction "1_1") (pintype "unspecified"))
      (node (ref "U9") (pin "20") (pinfunction "VCC_20") (pintype "unspecified"))
    )
    (net (code "56") (name "VCC_BAT") (class "Default")
      (node (ref "U1") (pin "1") (pinfunction "VBAT_1") (pintype "unspecified"))
      (node (ref "U13") (pin "1") (pinfunction "1_1") (pintype "unspecified"))
      (node (ref "U23") (pin "1") (pinfunction "+_1") (pintype "unspecified"))
      (node (ref "U24") (pin "1") (pinfunction "1_1") (pintype "unspecified"))
    )
    (net (code "57") (name "unconnected-(U2-NC-Pad4)") (class "Default")
      (node (ref "U2") (pin "4") (pinfunction "NC_4") (pintype "unspecified+no_connect"))
    )
    (net (code "58") (name "unconnected-(U10-NC-Pad3)") (class "Default")
      (node (ref "U10") (pin "3") (pinfunction "NC_3") (pintype "unspecified+no_connect"))
    )
    (net (code "59") (name "unconnected-(USB1-EH-Pad6)") (class "Default")
      (node (ref "USB1") (pin "6") (pinfunction "EH_6") (pintype "input+no_connect"))
    )
    (net (code "60") (name "unconnected-(USB1-ID-Pad4)") (class "Default")
      (node (ref "USB1") (pin "4") (pinfunction "ID_4") (pintype "input+no_connect"))
    )
  )
)
